# dual_encoder_shield_5v_revc.net
KiCad netlist of a schematic drawn in EAGLE
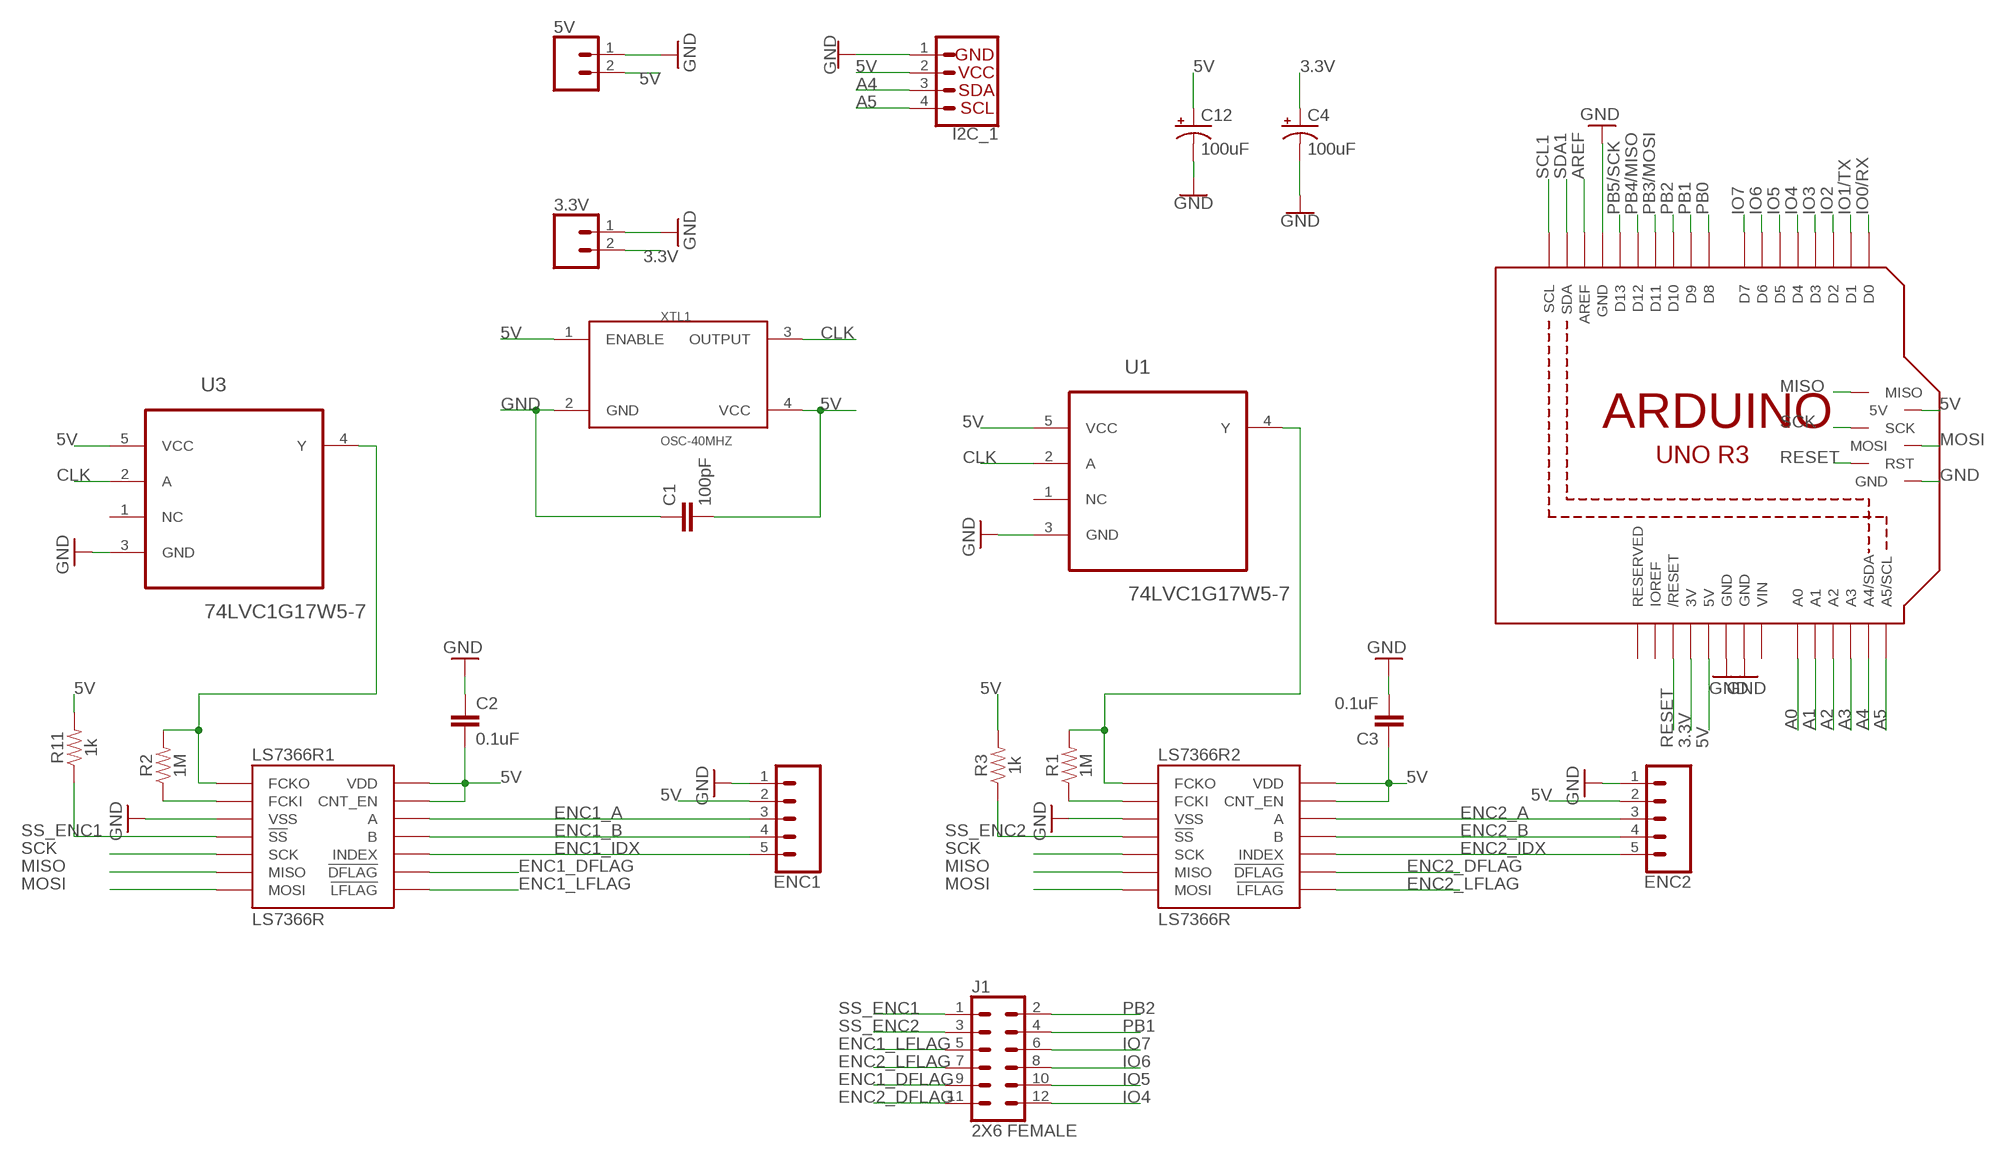
[diagram p0: schematic, sheet 1]

(export (version "E")
  (design (tool "Eeschema 10.0.6"))
  (components
    (comp (ref "3.3V")
      (value "CONN_02-JST-2MM-SMT")
      (footprint "eagle-import:JST-2-SMD")
      (libsource (lib "eagle-import") (part "CONN_02-JST-2MM-SMT"))
    )
    (comp (ref "5V")
      (value "CONN_02-JST-2MM-SMT")
      (footprint "eagle-import:JST-2-SMD")
      (libsource (lib "eagle-import") (part "CONN_02-JST-2MM-SMT"))
    )
    (comp (ref "C1")
      (value "100pF")
      (footprint "eagle-import:0603")
      (libsource (lib "eagle-import") (part "100PF-0603-50V-5%"))
    )
    (comp (ref "C2")
      (value "0.1uF")
      (footprint "eagle-import:0603")
      (libsource (lib "eagle-import") (part "0.1UF-0603-25V-5%"))
    )
    (comp (ref "C3")
      (value "0.1uF")
      (footprint "eagle-import:0603")
      (libsource (lib "eagle-import") (part "0.1UF-0603-25V-5%"))
    )
    (comp (ref "C4")
      (value "100uF")
      (footprint "eagle-import:PANASONIC_D")
      (libsource (lib "eagle-import") (part "100UF-POLAR-25V-20%(ELEC)"))
    )
    (comp (ref "C12")
      (value "100uF")
      (footprint "eagle-import:PANASONIC_D")
      (libsource (lib "eagle-import") (part "100UF-POLAR-25V-20%(ELEC)"))
    )
    (comp (ref "ENC1")
      (value "CONN_05")
      (footprint "eagle-import:1X05")
      (libsource (lib "eagle-import") (part "CONN_05"))
    )
    (comp (ref "ENC2")
      (value "CONN_05")
      (footprint "eagle-import:1X05")
      (libsource (lib "eagle-import") (part "CONN_05"))
    )
    (comp (ref "I2C_1")
      (value "QWIIC_CONNECTORJS-1MM")
      (footprint "eagle-import:JST04_1MM_RA")
      (libsource (lib "eagle-import") (part "QWIIC_CONNECTORJS-1MM"))
    )
    (comp (ref "J1")
      (value "2X6 FEMALE")
      (footprint "eagle-import:2X6")
      (libsource (lib "eagle-import") (part "CONN_06X2PTH_FEMALE"))
    )
    (comp (ref "LS7366R1")
      (value "LS7366R")
      (footprint "eagle-import:SOIC14")
      (fields (field (name "MF") "LSI"))
      (libsource (lib "eagle-import") (part "LS7366R"))
    )
    (comp (ref "LS7366R2")
      (value "LS7366R")
      (footprint "eagle-import:SOIC14")
      (fields (field (name "MF") "LSI"))
      (libsource (lib "eagle-import") (part "LS7366R"))
    )
    (comp (ref "M1")
      (value "ARDUINO_R3_ICSP")
      (footprint "eagle-import:ARDUINOR3_ICSP")
      (libsource (lib "eagle-import") (part "ARDUINO_R3_ICSP"))
    )
    (comp (ref "R1")
      (value "1M")
      (footprint "eagle-import:0603")
      (libsource (lib "eagle-import") (part "1MOHM-0603-1/4W-5%"))
    )
    (comp (ref "R2")
      (value "1M")
      (footprint "eagle-import:0603")
      (libsource (lib "eagle-import") (part "1MOHM-0603-1/4W-5%"))
    )
    (comp (ref "R3")
      (value "1k")
      (footprint "eagle-import:0603")
      (libsource (lib "eagle-import") (part "1KOHM-0603-1/10W-1%"))
    )
    (comp (ref "R11")
      (value "1k")
      (footprint "eagle-import:0603")
      (libsource (lib "eagle-import") (part "1KOHM-0603-1/10W-1%"))
    )
    (comp (ref "U1")
      (value "74LVC1G17W5-7")
      (footprint "eagle-import:SOT95P280X145-5N")
      (fields (field (name "DIGI-KEY_PART_NUMBER") "74LVC1G17W5-7TR-ND") (field (name "MF") "Diodes Inc."))
      (libsource (lib "eagle-import") (part "74LVC1G17W5-7"))
    )
    (comp (ref "U3")
      (value "74LVC1G17W5-7")
      (footprint "eagle-import:SOT95P280X145-5N")
      (fields (field (name "DIGI-KEY_PART_NUMBER") "74LVC1G17W5-7TR-ND") (field (name "MF") "Diodes Inc."))
      (libsource (lib "eagle-import") (part "74LVC1G17W5-7"))
    )
    (comp (ref "XTL1")
      (value "OSC-40MHZ")
      (footprint "eagle-import:OSC_CB3LV-5I-50M000000")
      (libsource (lib "eagle-import") (part "OSC-40MHZ"))
    )
  )
  (nets
    (net (code "1") (name "/3.3V") (class "Default")
      (node (ref "3.3V") (pin "2") (pinfunction "1_2") (pintype "passive"))
      (node (ref "C4") (pin "+") (pinfunction "+_+") (pintype "passive"))
      (node (ref "M1") (pin "3V") (pinfunction "3V_3V") (pintype "power_in"))
    )
    (net (code "2") (name "/5V") (class "Default")
      (node (ref "5V") (pin "2") (pinfunction "1_2") (pintype "passive"))
      (node (ref "C1") (pin "2") (pinfunction "2_2") (pintype "passive"))
      (node (ref "C12") (pin "+") (pinfunction "+_+") (pintype "passive"))
      (node (ref "C2") (pin "2") (pinfunction "2_2") (pintype "passive"))
      (node (ref "C3") (pin "1") (pinfunction "1_1") (pintype "passive"))
      (node (ref "ENC1") (pin "2") (pinfunction "2_2") (pintype "passive"))
      (node (ref "ENC2") (pin "2") (pinfunction "2_2") (pintype "passive"))
      (node (ref "I2C_1") (pin "2") (pinfunction "2_2") (pintype "power_in"))
      (node (ref "LS7366R1") (pin "13") (pinfunction "CNT_EN_13") (pintype "bidirectional"))
      (node (ref "LS7366R1") (pin "14") (pinfunction "VDD_14") (pintype "bidirectional"))
      (node (ref "LS7366R2") (pin "13") (pinfunction "CNT_EN_13") (pintype "bidirectional"))
      (node (ref "LS7366R2") (pin "14") (pinfunction "VDD_14") (pintype "bidirectional"))
      (node (ref "M1") (pin "5V") (pinfunction "5V_5V") (pintype "power_in"))
      (node (ref "M1") (pin "5V_ICSP") (pinfunction "5V_5V_ICSP") (pintype "passive"))
      (node (ref "R11") (pin "2") (pinfunction "2_2") (pintype "passive"))
      (node (ref "R3") (pin "2") (pinfunction "2_2") (pintype "passive"))
      (node (ref "U1") (pin "5") (pinfunction "VCC_5") (pintype "power_in"))
      (node (ref "U3") (pin "5") (pinfunction "VCC_5") (pintype "power_in"))
      (node (ref "XTL1") (pin "1") (pinfunction "ENABLE_1") (pintype "bidirectional"))
      (node (ref "XTL1") (pin "4") (pinfunction "VCC_4") (pintype "bidirectional"))
    )
    (net (code "3") (name "/A0") (class "Default")
      (node (ref "M1") (pin "A0") (pinfunction "A0_A0") (pintype "bidirectional"))
    )
    (net (code "4") (name "/A1") (class "Default")
      (node (ref "M1") (pin "A1") (pinfunction "A1_A1") (pintype "bidirectional"))
    )
    (net (code "5") (name "/A2") (class "Default")
      (node (ref "M1") (pin "A2") (pinfunction "A2_A2") (pintype "bidirectional"))
    )
    (net (code "6") (name "/A3") (class "Default")
      (node (ref "M1") (pin "A3") (pinfunction "A3_A3") (pintype "bidirectional"))
    )
    (net (code "7") (name "/A4") (class "Default")
      (node (ref "I2C_1") (pin "3") (pinfunction "3_3") (pintype "passive"))
      (node (ref "M1") (pin "A4") (pinfunction "A4/SDA_A4") (pintype "bidirectional"))
    )
    (net (code "8") (name "/A5") (class "Default")
      (node (ref "I2C_1") (pin "4") (pinfunction "4_4") (pintype "passive"))
      (node (ref "M1") (pin "A5") (pinfunction "A5/SCL_A5") (pintype "bidirectional"))
    )
    (net (code "9") (name "/AREF") (class "Default")
      (node (ref "M1") (pin "AREF") (pinfunction "AREF_AREF") (pintype "bidirectional"))
    )
    (net (code "10") (name "/CLK") (class "Default")
      (node (ref "U1") (pin "2") (pinfunction "A_2") (pintype "input"))
      (node (ref "U3") (pin "2") (pinfunction "A_2") (pintype "input"))
      (node (ref "XTL1") (pin "3") (pinfunction "OUTPUT_3") (pintype "bidirectional"))
    )
    (net (code "11") (name "/ENC1_A") (class "Default")
      (node (ref "ENC1") (pin "3") (pinfunction "3_3") (pintype "passive"))
      (node (ref "LS7366R1") (pin "12") (pinfunction "A_12") (pintype "bidirectional"))
    )
    (net (code "12") (name "/ENC1_B") (class "Default")
      (node (ref "ENC1") (pin "4") (pinfunction "4_4") (pintype "passive"))
      (node (ref "LS7366R1") (pin "11") (pinfunction "B_11") (pintype "bidirectional"))
    )
    (net (code "13") (name "/ENC1_DFLAG") (class "Default")
      (node (ref "J1") (pin "9") (pinfunction "9_9") (pintype "passive"))
      (node (ref "LS7366R1") (pin "9") (pinfunction "~{DFLAG}_9") (pintype "bidirectional"))
    )
    (net (code "14") (name "/ENC1_IDX") (class "Default")
      (node (ref "ENC1") (pin "5") (pinfunction "5_5") (pintype "passive"))
      (node (ref "LS7366R1") (pin "10") (pinfunction "INDEX_10") (pintype "bidirectional"))
    )
    (net (code "15") (name "/ENC1_LFLAG") (class "Default")
      (node (ref "J1") (pin "5") (pinfunction "5_5") (pintype "passive"))
      (node (ref "LS7366R1") (pin "8") (pinfunction "~{LFLAG}_8") (pintype "bidirectional"))
    )
    (net (code "16") (name "/ENC2_A") (class "Default")
      (node (ref "ENC2") (pin "3") (pinfunction "3_3") (pintype "passive"))
      (node (ref "LS7366R2") (pin "12") (pinfunction "A_12") (pintype "bidirectional"))
    )
    (net (code "17") (name "/ENC2_B") (class "Default")
      (node (ref "ENC2") (pin "4") (pinfunction "4_4") (pintype "passive"))
      (node (ref "LS7366R2") (pin "11") (pinfunction "B_11") (pintype "bidirectional"))
    )
    (net (code "18") (name "/ENC2_DFLAG") (class "Default")
      (node (ref "J1") (pin "11") (pinfunction "11_11") (pintype "passive"))
      (node (ref "LS7366R2") (pin "9") (pinfunction "~{DFLAG}_9") (pintype "bidirectional"))
    )
    (net (code "19") (name "/ENC2_IDX") (class "Default")
      (node (ref "ENC2") (pin "5") (pinfunction "5_5") (pintype "passive"))
      (node (ref "LS7366R2") (pin "10") (pinfunction "INDEX_10") (pintype "bidirectional"))
    )
    (net (code "20") (name "/ENC2_LFLAG") (class "Default")
      (node (ref "J1") (pin "7") (pinfunction "7_7") (pintype "passive"))
      (node (ref "LS7366R2") (pin "8") (pinfunction "~{LFLAG}_8") (pintype "bidirectional"))
    )
    (net (code "21") (name "/IO0{slash}RX") (class "Default")
      (node (ref "M1") (pin "D0") (pinfunction "D0_D0") (pintype "bidirectional"))
    )
    (net (code "22") (name "/IO1{slash}TX") (class "Default")
      (node (ref "M1") (pin "D1") (pinfunction "D1_D1") (pintype "bidirectional"))
    )
    (net (code "23") (name "/IO2") (class "Default")
      (node (ref "M1") (pin "D2") (pinfunction "D2_D2") (pintype "bidirectional"))
    )
    (net (code "24") (name "/IO3") (class "Default")
      (node (ref "M1") (pin "D3") (pinfunction "D3_D3") (pintype "bidirectional"))
    )
    (net (code "25") (name "/IO4") (class "Default")
      (node (ref "J1") (pin "12") (pinfunction "12_12") (pintype "passive"))
      (node (ref "M1") (pin "D4") (pinfunction "D4_D4") (pintype "bidirectional"))
    )
    (net (code "26") (name "/IO5") (class "Default")
      (node (ref "J1") (pin "10") (pinfunction "10_10") (pintype "passive"))
      (node (ref "M1") (pin "D5") (pinfunction "D5_D5") (pintype "bidirectional"))
    )
    (net (code "27") (name "/IO6") (class "Default")
      (node (ref "J1") (pin "8") (pinfunction "8_8") (pintype "passive"))
      (node (ref "M1") (pin "D6") (pinfunction "D6_D6") (pintype "bidirectional"))
    )
    (net (code "28") (name "/IO7") (class "Default")
      (node (ref "J1") (pin "6") (pinfunction "6_6") (pintype "passive"))
      (node (ref "M1") (pin "D7") (pinfunction "D7_D7") (pintype "bidirectional"))
    )
    (net (code "29") (name "/MISO") (class "Default")
      (node (ref "LS7366R1") (pin "6") (pinfunction "MISO_6") (pintype "bidirectional"))
      (node (ref "LS7366R2") (pin "6") (pinfunction "MISO_6") (pintype "bidirectional"))
      (node (ref "M1") (pin "MISO") (pinfunction "MISO_MISO") (pintype "passive"))
    )
    (net (code "30") (name "/MOSI") (class "Default")
      (node (ref "LS7366R1") (pin "7") (pinfunction "MOSI_7") (pintype "bidirectional"))
      (node (ref "LS7366R2") (pin "7") (pinfunction "MOSI_7") (pintype "bidirectional"))
      (node (ref "M1") (pin "MOSI") (pinfunction "MOSI_MOSI") (pintype "passive"))
    )
    (net (code "31") (name "/PB0") (class "Default")
      (node (ref "M1") (pin "D8") (pinfunction "D8_D8") (pintype "bidirectional"))
    )
    (net (code "32") (name "/PB1") (class "Default")
      (node (ref "J1") (pin "4") (pinfunction "4_4") (pintype "passive"))
      (node (ref "M1") (pin "D9") (pinfunction "D9_D9") (pintype "bidirectional"))
    )
    (net (code "33") (name "/PB2") (class "Default")
      (node (ref "J1") (pin "2") (pinfunction "2_2") (pintype "passive"))
      (node (ref "M1") (pin "D10") (pinfunction "D10_D10") (pintype "bidirectional"))
    )
    (net (code "34") (name "/PB3{slash}MOSI") (class "Default")
      (node (ref "M1") (pin "D11") (pinfunction "D11_D11") (pintype "bidirectional"))
    )
    (net (code "35") (name "/PB4{slash}MISO") (class "Default")
      (node (ref "M1") (pin "D12") (pinfunction "D12_D12") (pintype "bidirectional"))
    )
    (net (code "36") (name "/PB5{slash}SCK") (class "Default")
      (node (ref "M1") (pin "D13") (pinfunction "D13_D13") (pintype "bidirectional"))
    )
    (net (code "37") (name "/RESET") (class "Default")
      (node (ref "M1") (pin "RESET") (pinfunction "/RESET_RESET") (pintype "bidirectional"))
      (node (ref "M1") (pin "RESET_ICSP") (pinfunction "RST_RESET_ICSP") (pintype "passive"))
    )
    (net (code "38") (name "/SCK") (class "Default")
      (node (ref "LS7366R1") (pin "5") (pinfunction "SCK_5") (pintype "bidirectional"))
      (node (ref "LS7366R2") (pin "5") (pinfunction "SCK_5") (pintype "bidirectional"))
      (node (ref "M1") (pin "SCK") (pinfunction "SCK_SCK") (pintype "passive"))
    )
    (net (code "39") (name "/SCL1") (class "Default")
      (node (ref "M1") (pin "SCL") (pinfunction "SCL_SCL") (pintype "bidirectional"))
    )
    (net (code "40") (name "/SDA1") (class "Default")
      (node (ref "M1") (pin "SDA") (pinfunction "SDA_SDA") (pintype "bidirectional"))
    )
    (net (code "41") (name "/SS_ENC1") (class "Default")
      (node (ref "J1") (pin "1") (pinfunction "1_1") (pintype "passive"))
      (node (ref "LS7366R1") (pin "4") (pinfunction "~{SS}_4") (pintype "bidirectional"))
      (node (ref "R11") (pin "1") (pinfunction "1_1") (pintype "passive"))
    )
    (net (code "42") (name "/SS_ENC2") (class "Default")
      (node (ref "J1") (pin "3") (pinfunction "3_3") (pintype "passive"))
      (node (ref "LS7366R2") (pin "4") (pinfunction "~{SS}_4") (pintype "bidirectional"))
      (node (ref "R3") (pin "1") (pinfunction "1_1") (pintype "passive"))
    )
    (net (code "43") (name "/VIN") (class "Default")
      (node (ref "M1") (pin "VIN") (pinfunction "VIN_VIN") (pintype "power_in"))
    )
    (net (code "44") (name "GND") (class "Default")
      (node (ref "3.3V") (pin "1") (pinfunction "2_1") (pintype "passive"))
      (node (ref "5V") (pin "1") (pinfunction "2_1") (pintype "passive"))
      (node (ref "C1") (pin "1") (pinfunction "1_1") (pintype "passive"))
      (node (ref "C12") (pin "-") (pinfunction "-_-") (pintype "passive"))
      (node (ref "C2") (pin "1") (pinfunction "1_1") (pintype "passive"))
      (node (ref "C3") (pin "2") (pinfunction "2_2") (pintype "passive"))
      (node (ref "C4") (pin "-") (pinfunction "-_-") (pintype "passive"))
      (node (ref "ENC1") (pin "1") (pinfunction "1_1") (pintype "passive"))
      (node (ref "ENC2") (pin "1") (pinfunction "1_1") (pintype "passive"))
      (node (ref "I2C_1") (pin "1") (pinfunction "1_1") (pintype "power_in"))
      (node (ref "LS7366R1") (pin "3") (pinfunction "VSS_3") (pintype "bidirectional"))
      (node (ref "LS7366R2") (pin "3") (pinfunction "VSS_3") (pintype "bidirectional"))
      (node (ref "M1") (pin "GND") (pinfunction "GND_GND") (pintype "power_in"))
      (node (ref "M1") (pin "GND@1") (pinfunction "GND_GND@1") (pintype "power_in"))
      (node (ref "M1") (pin "GND@2") (pinfunction "GND_GND@2") (pintype "passive"))
      (node (ref "M1") (pin "GND@3") (pinfunction "GND_GND@3") (pintype "power_in"))
      (node (ref "U1") (pin "3") (pinfunction "GND_3") (pintype "passive"))
      (node (ref "U3") (pin "3") (pinfunction "GND_3") (pintype "passive"))
      (node (ref "XTL1") (pin "2") (pinfunction "GND_2") (pintype "bidirectional"))
    )
    (net (code "45") (name "Net-(LS7366R1-FCKI)") (class "Default")
      (node (ref "LS7366R1") (pin "2") (pinfunction "FCKI_2") (pintype "bidirectional"))
      (node (ref "R2") (pin "1") (pinfunction "1_1") (pintype "passive"))
    )
    (net (code "46") (name "Net-(LS7366R1-FCKO)") (class "Default")
      (node (ref "LS7366R1") (pin "1") (pinfunction "FCKO_1") (pintype "bidirectional"))
      (node (ref "R2") (pin "2") (pinfunction "2_2") (pintype "passive"))
      (node (ref "U3") (pin "4") (pinfunction "Y_4") (pintype "output"))
    )
    (net (code "47") (name "Net-(LS7366R2-FCKI)") (class "Default")
      (node (ref "LS7366R2") (pin "2") (pinfunction "FCKI_2") (pintype "bidirectional"))
      (node (ref "R1") (pin "1") (pinfunction "1_1") (pintype "passive"))
    )
    (net (code "48") (name "Net-(LS7366R2-FCKO)") (class "Default")
      (node (ref "LS7366R2") (pin "1") (pinfunction "FCKO_1") (pintype "bidirectional"))
      (node (ref "R1") (pin "2") (pinfunction "2_2") (pintype "passive"))
      (node (ref "U1") (pin "4") (pinfunction "Y_4") (pintype "output"))
    )
    (net (code "49") (name "unconnected-(M1-PadIOREF)") (class "Default")
      (node (ref "M1") (pin "IOREF") (pinfunction "IOREF_IOREF") (pintype "output"))
    )
    (net (code "50") (name "unconnected-(M1-PadRESERVED)") (class "Default")
      (node (ref "M1") (pin "RESERVED") (pinfunction "RESERVED_RESERVED") (pintype "no_connect"))
    )
    (net (code "51") (name "unconnected-(U1-NC-Pad1)") (class "Default")
      (node (ref "U1") (pin "1") (pinfunction "NC_1") (pintype "no_connect"))
    )
    (net (code "52") (name "unconnected-(U3-NC-Pad1)") (class "Default")
      (node (ref "U3") (pin "1") (pinfunction "NC_1") (pintype "no_connect"))
    )
  )
)
